# Esquematico.net
KiCad netlist of a schematic drawn in Altium Designer
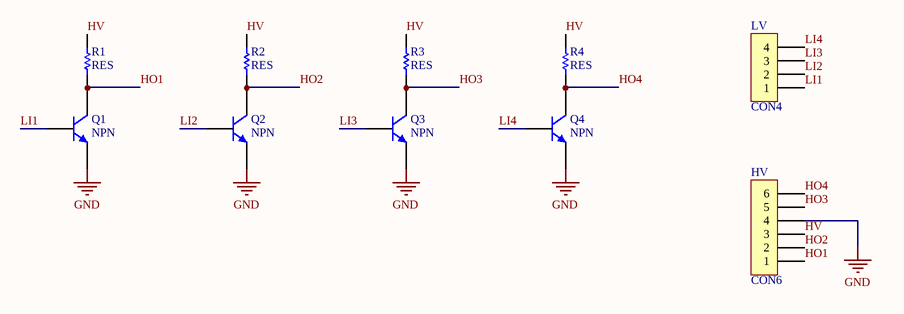
[diagram p0: Esquematico.SchDoc]

(export (version "E")
  (design (tool "Eeschema 10.0.6"))
  (components
    (comp (ref "HV") (value "CON6") (footprint "SIP6") (libsource (lib "LIBEBAL") (part "CON6")))
    (comp (ref "LV") (value "CON4") (footprint "SIP4") (libsource (lib "LIBEBAL") (part "CON4")))
    (comp (ref "Q1")
      (value "NPN")
      (footprint "TO-226-AA")
      (description "NPN Bipolar Transistor")
      (fields (field (name "PUBLISHER") "Altium Limited"))
      (libsource (lib "Miscellaneous Devices") (part "NPN"))
    )
    (comp (ref "Q2")
      (value "NPN")
      (footprint "TO-226-AA")
      (description "NPN Bipolar Transistor")
      (fields (field (name "PUBLISHER") "Altium Limited"))
      (libsource (lib "Miscellaneous Devices") (part "NPN"))
    )
    (comp (ref "Q3")
      (value "NPN")
      (footprint "TO-226-AA")
      (description "NPN Bipolar Transistor")
      (fields (field (name "PUBLISHER") "Altium Limited"))
      (libsource (lib "Miscellaneous Devices") (part "NPN"))
    )
    (comp (ref "Q4")
      (value "NPN")
      (footprint "TO-226-AA")
      (description "NPN Bipolar Transistor")
      (fields (field (name "PUBLISHER") "Altium Limited"))
      (libsource (lib "Miscellaneous Devices") (part "NPN"))
    )
    (comp (ref "R1") (value "RES") (footprint "RES400") (libsource (lib "LIBEBAL") (part "RES")))
    (comp (ref "R2") (value "RES") (footprint "RES400") (libsource (lib "LIBEBAL") (part "RES")))
    (comp (ref "R3") (value "RES") (footprint "RES400") (libsource (lib "LIBEBAL") (part "RES")))
    (comp (ref "R4") (value "RES") (footprint "RES400") (libsource (lib "LIBEBAL") (part "RES")))
  )
  (nets
    (net (code "1") (name "/HO1") (class "Default")
      (node (ref "HV") (pin "1") (pinfunction "1_1") (pintype "passive"))
      (node (ref "Q1") (pin "1") (pinfunction "C_1") (pintype "passive"))
      (node (ref "R1") (pin "1") (pinfunction "1_1") (pintype "passive"))
    )
    (net (code "2") (name "/HO2") (class "Default")
      (node (ref "HV") (pin "2") (pinfunction "2_2") (pintype "passive"))
      (node (ref "Q2") (pin "1") (pinfunction "C_1") (pintype "passive"))
      (node (ref "R2") (pin "1") (pinfunction "1_1") (pintype "passive"))
    )
    (net (code "3") (name "/HO3") (class "Default")
      (node (ref "HV") (pin "5") (pinfunction "5_5") (pintype "passive"))
      (node (ref "Q3") (pin "1") (pinfunction "C_1") (pintype "passive"))
      (node (ref "R3") (pin "1") (pinfunction "1_1") (pintype "passive"))
    )
    (net (code "4") (name "/HO4") (class "Default")
      (node (ref "HV") (pin "6") (pinfunction "6_6") (pintype "passive"))
      (node (ref "Q4") (pin "1") (pinfunction "C_1") (pintype "passive"))
      (node (ref "R4") (pin "1") (pinfunction "1_1") (pintype "passive"))
    )
    (net (code "5") (name "/HV") (class "Default")
      (node (ref "HV") (pin "3") (pinfunction "3_3") (pintype "passive"))
      (node (ref "R1") (pin "2") (pinfunction "2_2") (pintype "passive"))
      (node (ref "R2") (pin "2") (pinfunction "2_2") (pintype "passive"))
      (node (ref "R3") (pin "2") (pinfunction "2_2") (pintype "passive"))
      (node (ref "R4") (pin "2") (pinfunction "2_2") (pintype "passive"))
    )
    (net (code "6") (name "/LI1") (class "Default")
      (node (ref "LV") (pin "1") (pinfunction "1_1") (pintype "passive"))
      (node (ref "Q1") (pin "2") (pinfunction "B_2") (pintype "passive"))
    )
    (net (code "7") (name "/LI2") (class "Default")
      (node (ref "LV") (pin "2") (pinfunction "2_2") (pintype "passive"))
      (node (ref "Q2") (pin "2") (pinfunction "B_2") (pintype "passive"))
    )
    (net (code "8") (name "/LI3") (class "Default")
      (node (ref "LV") (pin "3") (pinfunction "3_3") (pintype "passive"))
      (node (ref "Q3") (pin "2") (pinfunction "B_2") (pintype "passive"))
    )
    (net (code "9") (name "/LI4") (class "Default")
      (node (ref "LV") (pin "4") (pinfunction "4_4") (pintype "passive"))
      (node (ref "Q4") (pin "2") (pinfunction "B_2") (pintype "passive"))
    )
    (net (code "10") (name "GND") (class "Default")
      (node (ref "HV") (pin "4") (pinfunction "4_4") (pintype "passive"))
      (node (ref "Q1") (pin "3") (pinfunction "E_3") (pintype "passive"))
      (node (ref "Q2") (pin "3") (pinfunction "E_3") (pintype "passive"))
      (node (ref "Q3") (pin "3") (pinfunction "E_3") (pintype "passive"))
      (node (ref "Q4") (pin "3") (pinfunction "E_3") (pintype "passive"))
    )
  )
)
